# mainboard.net
KiCad netlist of a schematic drawn in EAGLE
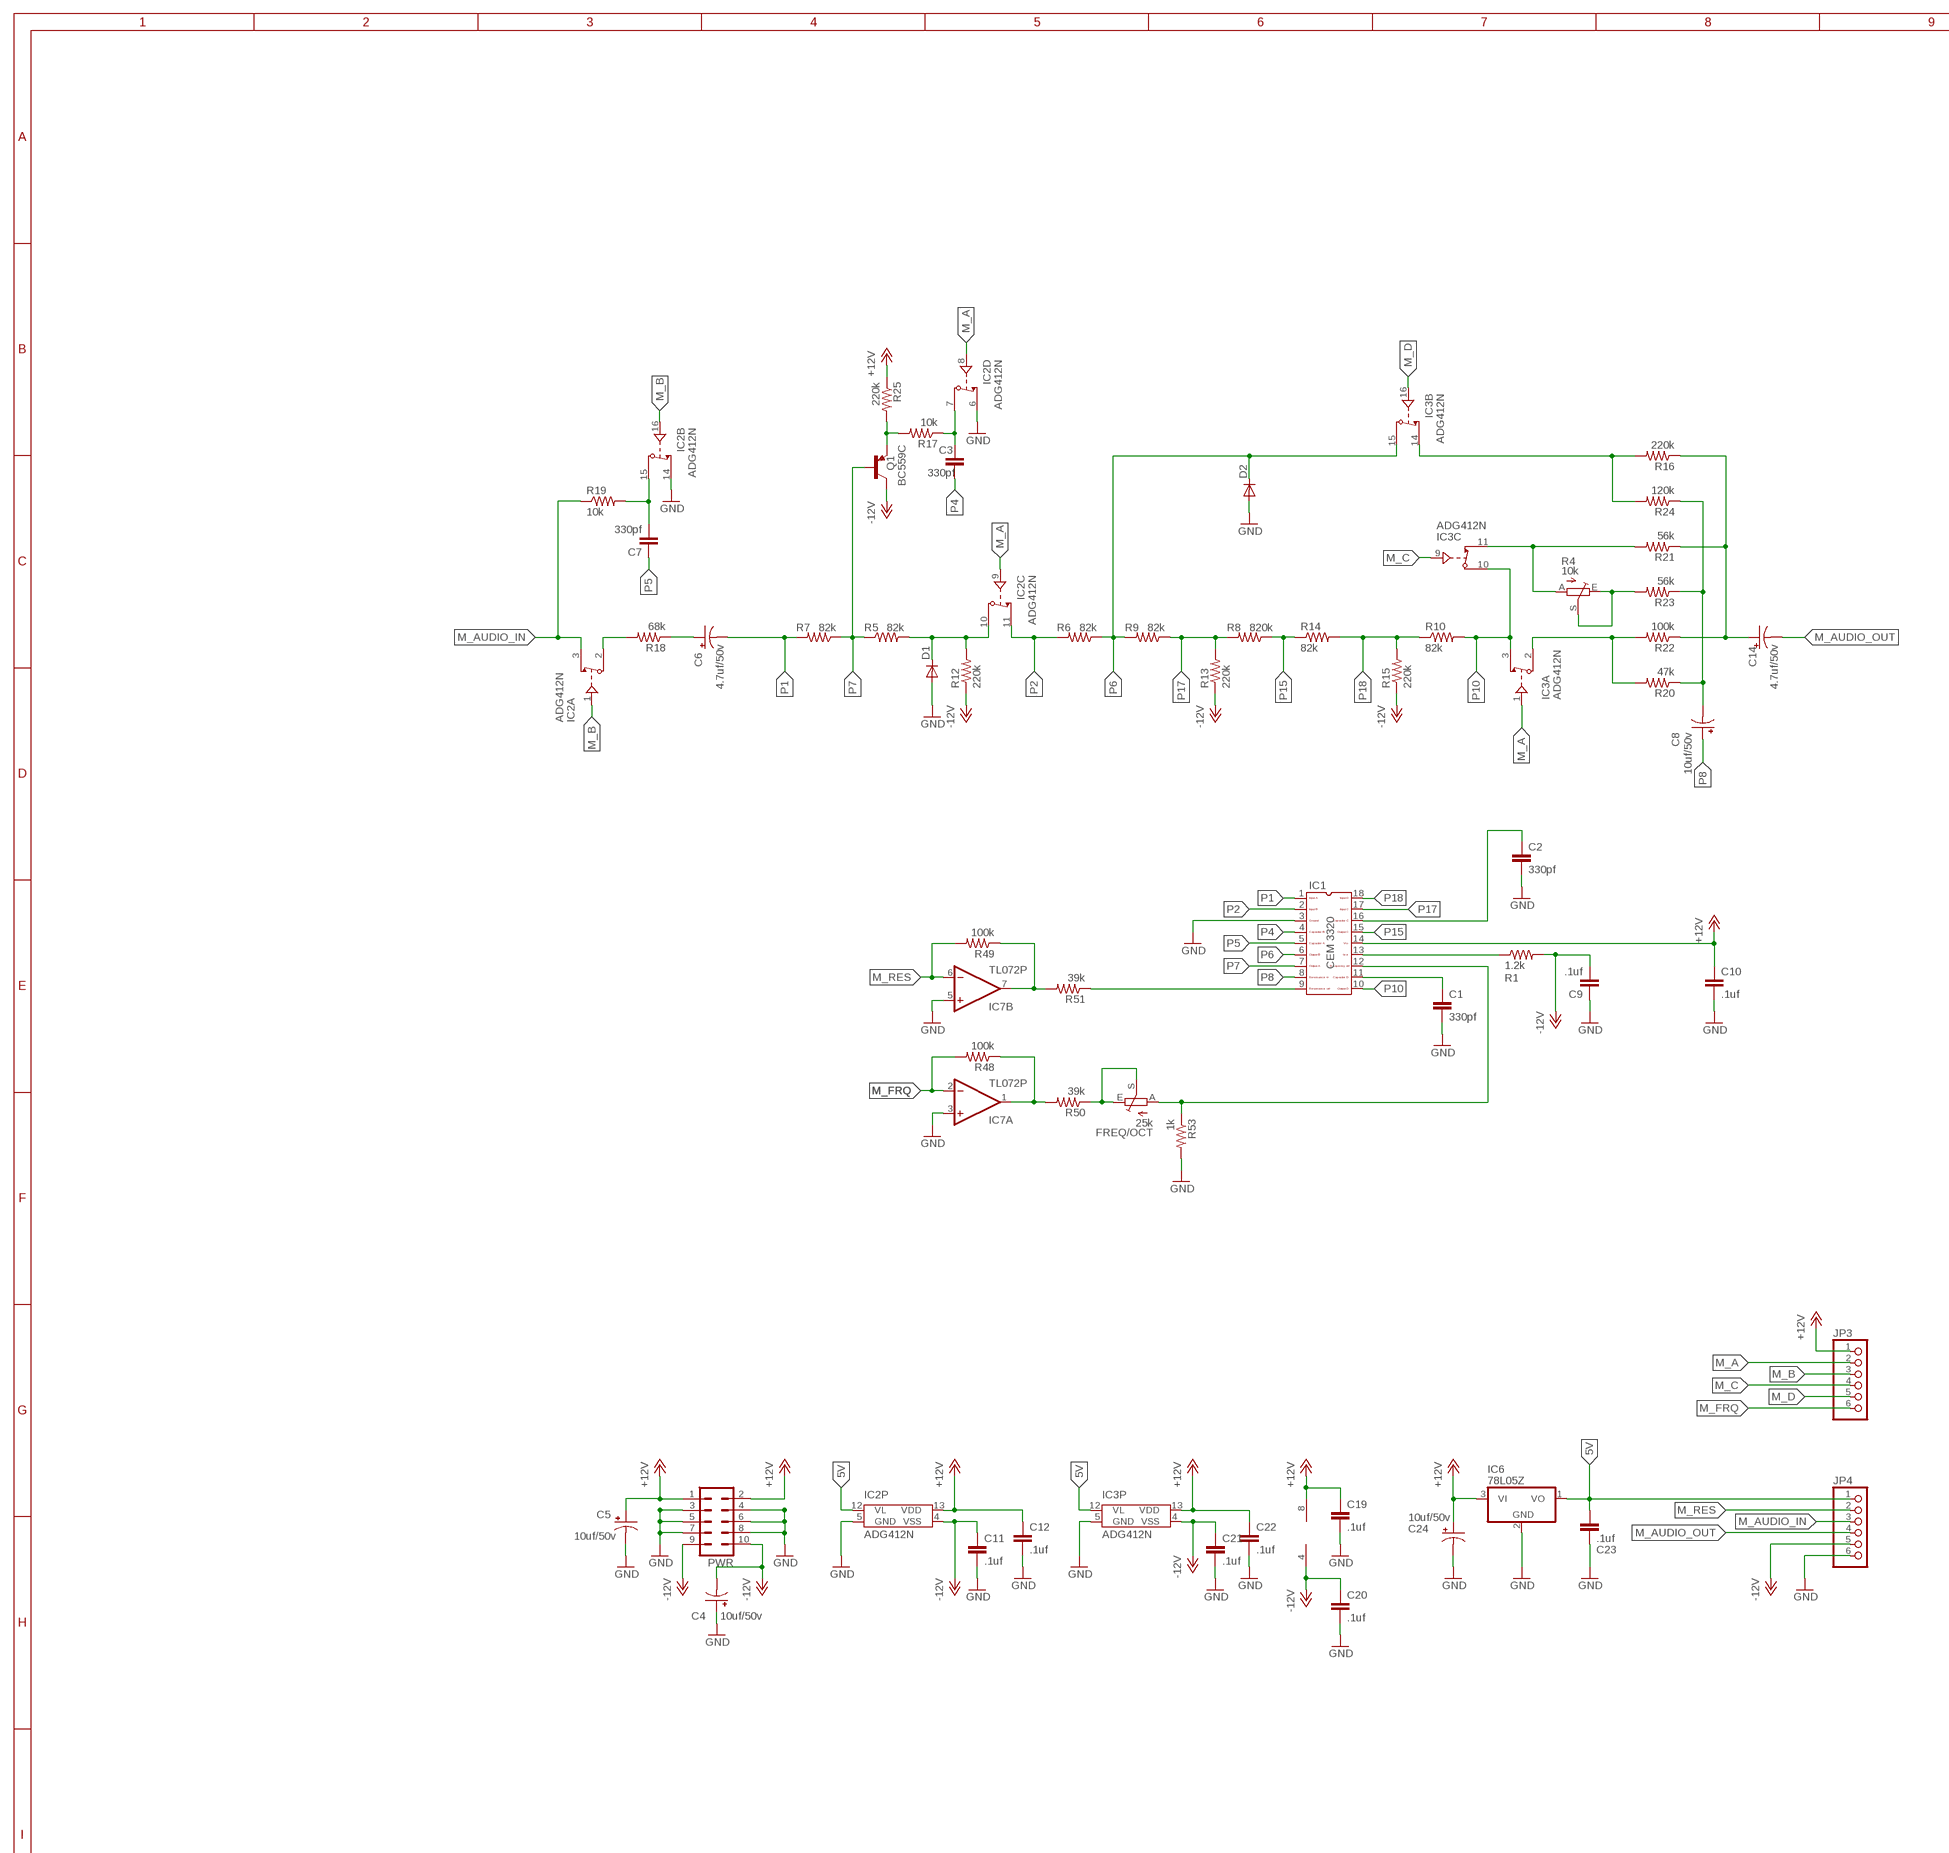
[diagram p0: schematic, sheet 1, part 1 of 2]
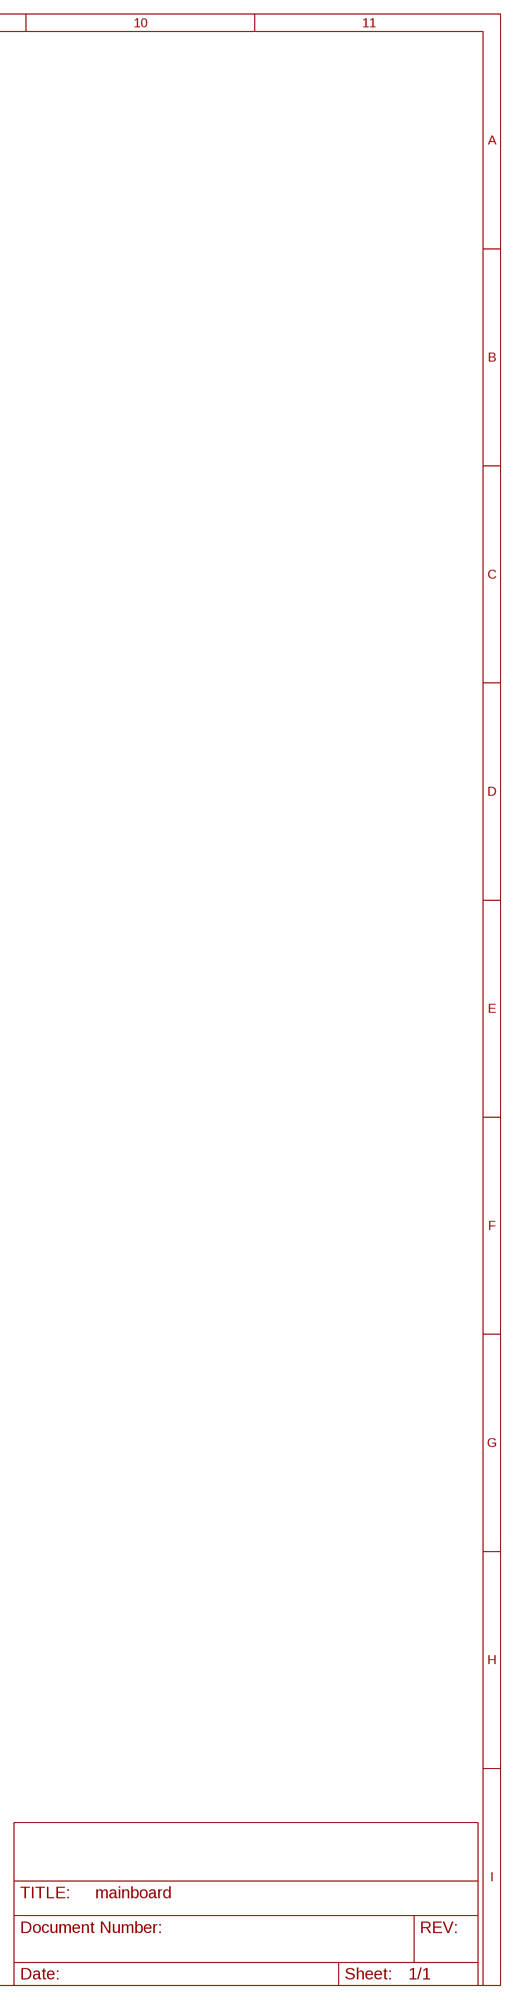
[diagram p1: schematic, sheet 1, part 2 of 2]

(export (version "E")
  (design (tool "Eeschema 10.0.6"))
  (components
    (comp (ref "C1")
      (value "330pf")
      (footprint "eagle-import:C050-050X075")
      (libsource (lib "eagle-import") (part "C-EU050-050X075"))
    )
    (comp (ref "C2")
      (value "330pf")
      (footprint "eagle-import:C050-050X075")
      (libsource (lib "eagle-import") (part "C-EU050-050X075"))
    )
    (comp (ref "C3")
      (value "330pf")
      (footprint "eagle-import:C050-050X075")
      (libsource (lib "eagle-import") (part "C-EU050-050X075"))
    )
    (comp (ref "C4")
      (value "10uf/50v")
      (footprint "eagle-import:E2,5-5")
      (libsource (lib "eagle-import") (part "CPOL-USE2.5-5"))
    )
    (comp (ref "C5")
      (value "10uf/50v")
      (footprint "eagle-import:E2,5-5")
      (libsource (lib "eagle-import") (part "CPOL-USE2.5-5"))
    )
    (comp (ref "C6")
      (value "4.7uf/50v")
      (footprint "eagle-import:E2,5-5")
      (libsource (lib "eagle-import") (part "CPOL-USE2.5-5"))
    )
    (comp (ref "C7")
      (value "330pf")
      (footprint "eagle-import:C050-050X075")
      (libsource (lib "eagle-import") (part "C-EU050-050X075"))
    )
    (comp (ref "C8")
      (value "10uf/50v")
      (footprint "eagle-import:E2,5-5")
      (libsource (lib "eagle-import") (part "CPOL-USE2.5-5"))
    )
    (comp (ref "C9")
      (value ".1uf")
      (footprint "eagle-import:C050-024X044")
      (libsource (lib "eagle-import") (part "resistor_C-EU050-024X044"))
    )
    (comp (ref "C10")
      (value ".1uf")
      (footprint "eagle-import:C050-024X044")
      (libsource (lib "eagle-import") (part "resistor_C-EU050-024X044"))
    )
    (comp (ref "C11")
      (value ".1uf")
      (footprint "eagle-import:C050-024X044")
      (libsource (lib "eagle-import") (part "resistor_C-EU050-024X044"))
    )
    (comp (ref "C12")
      (value ".1uf")
      (footprint "eagle-import:C050-024X044")
      (libsource (lib "eagle-import") (part "resistor_C-EU050-024X044"))
    )
    (comp (ref "C14")
      (value "4.7uf/50v")
      (footprint "eagle-import:E2,5-5")
      (libsource (lib "eagle-import") (part "CPOL-USE2.5-5"))
    )
    (comp (ref "C19")
      (value ".1uf")
      (footprint "eagle-import:C050-024X044")
      (libsource (lib "eagle-import") (part "resistor_C-EU050-024X044"))
    )
    (comp (ref "C20")
      (value ".1uf")
      (footprint "eagle-import:C050-024X044")
      (libsource (lib "eagle-import") (part "resistor_C-EU050-024X044"))
    )
    (comp (ref "C21")
      (value ".1uf")
      (footprint "eagle-import:C050-024X044")
      (libsource (lib "eagle-import") (part "resistor_C-EU050-024X044"))
    )
    (comp (ref "C22")
      (value ".1uf")
      (footprint "eagle-import:C050-024X044")
      (libsource (lib "eagle-import") (part "resistor_C-EU050-024X044"))
    )
    (comp (ref "C23")
      (value ".1uf")
      (footprint "eagle-import:C050-024X044")
      (libsource (lib "eagle-import") (part "resistor_C-EU050-024X044"))
    )
    (comp (ref "C24")
      (value "10uf/50v")
      (footprint "eagle-import:E2,5-5")
      (libsource (lib "eagle-import") (part "CPOL-USE2.5-5"))
    )
    (comp (ref "D1")
      (value "1N4148DO35-7")
      (footprint "eagle-import:DO35-7")
      (libsource (lib "eagle-import") (part "1N4148DO35-7"))
    )
    (comp (ref "D2")
      (value "1N4148DO35-7")
      (footprint "eagle-import:DO35-7")
      (libsource (lib "eagle-import") (part "1N4148DO35-7"))
    )
    (comp (ref "FREQ/OCT")
      (value "25k")
      (footprint "eagle-import:S64YW")
      (libsource (lib "eagle-import") (part "TRIM_1234-S64YW"))
    )
    (comp (ref "IC1")
      (value "CEM3320")
      (footprint "eagle-import:DIL18")
      (libsource (lib "eagle-import") (part "CEM3320"))
    )
    (comp (ref "IC2")
      (value "ADG412N")
      (footprint "eagle-import:DIL16")
      (fields (field (name "MF") "ALTERA CORPORATION") (field (name "MPN") "ADG412TQ"))
      (libsource (lib "eagle-import") (part "ADG412N"))
    )
    (comp (ref "IC3")
      (value "ADG412N")
      (footprint "eagle-import:DIL16")
      (fields (field (name "MF") "ALTERA CORPORATION") (field (name "MPN") "ADG412TQ"))
      (libsource (lib "eagle-import") (part "ADG412N"))
    )
    (comp (ref "IC6")
      (value "78L05Z")
      (footprint "eagle-import:TO92")
      (libsource (lib "eagle-import") (part "78ZL05"))
    )
    (comp (ref "IC7")
      (value "TL072P")
      (footprint "eagle-import:DIL08")
      (libsource (lib "eagle-import") (part "TL072P"))
    )
    (comp (ref "JP3")
      (value "PINHD-1X6")
      (footprint "eagle-import:1X06")
      (libsource (lib "eagle-import") (part "PINHD-1X6"))
    )
    (comp (ref "JP4")
      (value "PINHD-1X6")
      (footprint "eagle-import:1X06")
      (libsource (lib "eagle-import") (part "PINHD-1X6"))
    )
    (comp (ref "PWR")
      (value "ML10")
      (footprint "eagle-import:ML10")
      (libsource (lib "eagle-import") (part "ML10"))
    )
    (comp (ref "Q1")
      (value "BC559C")
      (footprint "eagle-import:TO92-EBC")
      (libsource (lib "eagle-import") (part "BC559C"))
    )
    (comp (ref "R1")
      (value "1.2k")
      (footprint "eagle-import:0207_10")
      (libsource (lib "eagle-import") (part "R-US_0207/10"))
    )
    (comp (ref "R4")
      (value "10k")
      (footprint "eagle-import:S64YW")
      (libsource (lib "eagle-import") (part "TRIM_1234-S64YW"))
    )
    (comp (ref "R5")
      (value "82k")
      (footprint "eagle-import:0207_10")
      (libsource (lib "eagle-import") (part "R-US_0207/10"))
    )
    (comp (ref "R6")
      (value "82k")
      (footprint "eagle-import:0207_10")
      (libsource (lib "eagle-import") (part "R-US_0207/10"))
    )
    (comp (ref "R7")
      (value "82k")
      (footprint "eagle-import:0207_10")
      (libsource (lib "eagle-import") (part "R-US_0207/10"))
    )
    (comp (ref "R8")
      (value "820k")
      (footprint "eagle-import:0207_10")
      (libsource (lib "eagle-import") (part "R-US_0207/10"))
    )
    (comp (ref "R9")
      (value "82k")
      (footprint "eagle-import:0207_10")
      (libsource (lib "eagle-import") (part "R-US_0207/10"))
    )
    (comp (ref "R10")
      (value "82k")
      (footprint "eagle-import:0207_10")
      (libsource (lib "eagle-import") (part "R-US_0207/10"))
    )
    (comp (ref "R12")
      (value "220k")
      (footprint "eagle-import:0207_10")
      (libsource (lib "eagle-import") (part "R-US_0207/10"))
    )
    (comp (ref "R13")
      (value "220k")
      (footprint "eagle-import:0207_10")
      (libsource (lib "eagle-import") (part "R-US_0207/10"))
    )
    (comp (ref "R14")
      (value "82k")
      (footprint "eagle-import:0207_10")
      (libsource (lib "eagle-import") (part "R-US_0207/10"))
    )
    (comp (ref "R15")
      (value "220k")
      (footprint "eagle-import:0207_10")
      (libsource (lib "eagle-import") (part "R-US_0207/10"))
    )
    (comp (ref "R16")
      (value "220k")
      (footprint "eagle-import:0207_10")
      (libsource (lib "eagle-import") (part "R-US_0207/10"))
    )
    (comp (ref "R17")
      (value "10k")
      (footprint "eagle-import:0207_10")
      (libsource (lib "eagle-import") (part "R-US_0207/10"))
    )
    (comp (ref "R18")
      (value "68k")
      (footprint "eagle-import:0207_10")
      (libsource (lib "eagle-import") (part "R-US_0207/10"))
    )
    (comp (ref "R19")
      (value "10k")
      (footprint "eagle-import:0207_10")
      (libsource (lib "eagle-import") (part "R-US_0207/10"))
    )
    (comp (ref "R20")
      (value "47k")
      (footprint "eagle-import:0207_10")
      (libsource (lib "eagle-import") (part "R-US_0207/10"))
    )
    (comp (ref "R21")
      (value "56k")
      (footprint "eagle-import:0207_10")
      (libsource (lib "eagle-import") (part "R-US_0207/10"))
    )
    (comp (ref "R22")
      (value "100k")
      (footprint "eagle-import:0207_10")
      (libsource (lib "eagle-import") (part "R-US_0207/10"))
    )
    (comp (ref "R23")
      (value "56k")
      (footprint "eagle-import:0207_10")
      (libsource (lib "eagle-import") (part "R-US_0207/10"))
    )
    (comp (ref "R24")
      (value "120k")
      (footprint "eagle-import:0207_10")
      (libsource (lib "eagle-import") (part "R-US_0207/10"))
    )
    (comp (ref "R25")
      (value "220k")
      (footprint "eagle-import:0207_10")
      (libsource (lib "eagle-import") (part "R-US_0207/10"))
    )
    (comp (ref "R48")
      (value "100k")
      (footprint "eagle-import:0207_10")
      (libsource (lib "eagle-import") (part "R-US_0207/10"))
    )
    (comp (ref "R49")
      (value "100k")
      (footprint "eagle-import:0207_10")
      (libsource (lib "eagle-import") (part "R-US_0207/10"))
    )
    (comp (ref "R50")
      (value "39k")
      (footprint "eagle-import:0207_10")
      (libsource (lib "eagle-import") (part "R-US_0207/10"))
    )
    (comp (ref "R51")
      (value "39k")
      (footprint "eagle-import:0207_10")
      (libsource (lib "eagle-import") (part "R-US_0207/10"))
    )
    (comp (ref "R53")
      (value "1k")
      (footprint "eagle-import:0207_10")
      (libsource (lib "eagle-import") (part "R-US_0207/10"))
    )
  )
  (nets
    (net (code "1") (name "+12V") (class "Default")
      (node (ref "C10") (pin "1") (pinfunction "1_1") (pintype "passive"))
      (node (ref "C12") (pin "1") (pinfunction "1_1") (pintype "passive"))
      (node (ref "C19") (pin "1") (pinfunction "1_1") (pintype "passive"))
      (node (ref "C22") (pin "1") (pinfunction "1_1") (pintype "passive"))
      (node (ref "C24") (pin "+") (pinfunction "+_+") (pintype "passive"))
      (node (ref "C5") (pin "+") (pinfunction "+_+") (pintype "passive"))
      (node (ref "IC1") (pin "14") (pinfunction "14_14") (pintype "power_in"))
      (node (ref "IC2") (pin "13") (pinfunction "VDD_13") (pintype "power_in"))
      (node (ref "IC3") (pin "13") (pinfunction "VDD_13") (pintype "power_in"))
      (node (ref "IC6") (pin "3") (pinfunction "VI_3") (pintype "input"))
      (node (ref "IC7") (pin "8") (pinfunction "V+_8") (pintype "power_in"))
      (node (ref "JP3") (pin "1") (pinfunction "1_1") (pintype "passive"))
      (node (ref "PWR") (pin "1") (pinfunction "1_1") (pintype "passive"))
      (node (ref "PWR") (pin "2") (pinfunction "2_2") (pintype "passive"))
      (node (ref "R25") (pin "1") (pinfunction "1_1") (pintype "passive"))
    )
    (net (code "2") (name "-12V") (class "Default")
      (node (ref "C11") (pin "1") (pinfunction "1_1") (pintype "passive"))
      (node (ref "C20") (pin "1") (pinfunction "1_1") (pintype "passive"))
      (node (ref "C21") (pin "1") (pinfunction "1_1") (pintype "passive"))
      (node (ref "C4") (pin "-") (pinfunction "-_-") (pintype "passive"))
      (node (ref "C9") (pin "2") (pinfunction "2_2") (pintype "passive"))
      (node (ref "IC2") (pin "4") (pinfunction "VSS_4") (pintype "power_in"))
      (node (ref "IC3") (pin "4") (pinfunction "VSS_4") (pintype "power_in"))
      (node (ref "IC7") (pin "4") (pinfunction "V-_4") (pintype "power_in"))
      (node (ref "JP4") (pin "5") (pinfunction "5_5") (pintype "passive"))
      (node (ref "PWR") (pin "10") (pinfunction "10_10") (pintype "passive"))
      (node (ref "PWR") (pin "9") (pinfunction "9_9") (pintype "passive"))
      (node (ref "Q1") (pin "C") (pinfunction "C_C") (pintype "passive"))
      (node (ref "R1") (pin "2") (pinfunction "2_2") (pintype "passive"))
      (node (ref "R12") (pin "1") (pinfunction "1_1") (pintype "passive"))
      (node (ref "R13") (pin "1") (pinfunction "1_1") (pintype "passive"))
      (node (ref "R15") (pin "1") (pinfunction "1_1") (pintype "passive"))
    )
    (net (code "3") (name "5V") (class "Default")
      (node (ref "C23") (pin "1") (pinfunction "1_1") (pintype "passive"))
      (node (ref "IC2") (pin "12") (pinfunction "VL_12") (pintype "power_in"))
      (node (ref "IC3") (pin "12") (pinfunction "VL_12") (pintype "power_in"))
      (node (ref "IC6") (pin "1") (pinfunction "VO_1") (pintype "passive"))
      (node (ref "JP4") (pin "1") (pinfunction "1_1") (pintype "passive"))
    )
    (net (code "4") (name "GND") (class "Default")
      (node (ref "C1") (pin "1") (pinfunction "1_1") (pintype "passive"))
      (node (ref "C10") (pin "2") (pinfunction "2_2") (pintype "passive"))
      (node (ref "C11") (pin "2") (pinfunction "2_2") (pintype "passive"))
      (node (ref "C12") (pin "2") (pinfunction "2_2") (pintype "passive"))
      (node (ref "C19") (pin "2") (pinfunction "2_2") (pintype "passive"))
      (node (ref "C2") (pin "2") (pinfunction "2_2") (pintype "passive"))
      (node (ref "C20") (pin "2") (pinfunction "2_2") (pintype "passive"))
      (node (ref "C21") (pin "2") (pinfunction "2_2") (pintype "passive"))
      (node (ref "C22") (pin "2") (pinfunction "2_2") (pintype "passive"))
      (node (ref "C23") (pin "2") (pinfunction "2_2") (pintype "passive"))
      (node (ref "C24") (pin "-") (pinfunction "-_-") (pintype "passive"))
      (node (ref "C4") (pin "+") (pinfunction "+_+") (pintype "passive"))
      (node (ref "C5") (pin "-") (pinfunction "-_-") (pintype "passive"))
      (node (ref "C9") (pin "1") (pinfunction "1_1") (pintype "passive"))
      (node (ref "D1") (pin "A") (pinfunction "A_A") (pintype "passive"))
      (node (ref "D2") (pin "A") (pinfunction "A_A") (pintype "passive"))
      (node (ref "IC1") (pin "3") (pinfunction "3_3") (pintype "power_in"))
      (node (ref "IC2") (pin "14") (pinfunction "S_14") (pintype "passive"))
      (node (ref "IC2") (pin "5") (pinfunction "GND_5") (pintype "power_in"))
      (node (ref "IC2") (pin "6") (pinfunction "S_6") (pintype "passive"))
      (node (ref "IC3") (pin "5") (pinfunction "GND_5") (pintype "power_in"))
      (node (ref "IC6") (pin "2") (pinfunction "GND_2") (pintype "passive"))
      (node (ref "IC7") (pin "3") (pinfunction "+IN_3") (pintype "input"))
      (node (ref "IC7") (pin "5") (pinfunction "+IN_5") (pintype "input"))
      (node (ref "JP4") (pin "6") (pinfunction "6_6") (pintype "passive"))
      (node (ref "PWR") (pin "3") (pinfunction "3_3") (pintype "passive"))
      (node (ref "PWR") (pin "4") (pinfunction "4_4") (pintype "passive"))
      (node (ref "PWR") (pin "5") (pinfunction "5_5") (pintype "passive"))
      (node (ref "PWR") (pin "6") (pinfunction "6_6") (pintype "passive"))
      (node (ref "PWR") (pin "7") (pinfunction "7_7") (pintype "passive"))
      (node (ref "PWR") (pin "8") (pinfunction "8_8") (pintype "passive"))
      (node (ref "R53") (pin "2") (pinfunction "2_2") (pintype "passive"))
    )
    (net (code "5") (name "M_A") (class "Default")
      (node (ref "IC2") (pin "8") (pinfunction "IN_8") (pintype "input"))
      (node (ref "IC2") (pin "9") (pinfunction "IN_9") (pintype "input"))
      (node (ref "IC3") (pin "1") (pinfunction "IN_1") (pintype "input"))
      (node (ref "JP3") (pin "2") (pinfunction "2_2") (pintype "passive"))
    )
    (net (code "6") (name "M_AUDIO_IN") (class "Default")
      (node (ref "IC2") (pin "3") (pinfunction "S_3") (pintype "passive"))
      (node (ref "JP4") (pin "3") (pinfunction "3_3") (pintype "passive"))
      (node (ref "R19") (pin "1") (pinfunction "1_1") (pintype "passive"))
    )
    (net (code "7") (name "M_AUDIO_OUT") (class "Default")
      (node (ref "C14") (pin "-") (pinfunction "-_-") (pintype "passive"))
      (node (ref "JP4") (pin "4") (pinfunction "4_4") (pintype "passive"))
    )
    (net (code "8") (name "M_B") (class "Default")
      (node (ref "IC2") (pin "1") (pinfunction "IN_1") (pintype "input"))
      (node (ref "IC2") (pin "16") (pinfunction "IN_16") (pintype "input"))
      (node (ref "JP3") (pin "3") (pinfunction "3_3") (pintype "passive"))
    )
    (net (code "9") (name "M_C") (class "Default")
      (node (ref "IC3") (pin "9") (pinfunction "IN_9") (pintype "input"))
      (node (ref "JP3") (pin "4") (pinfunction "4_4") (pintype "passive"))
    )
    (net (code "10") (name "M_D") (class "Default")
      (node (ref "IC3") (pin "16") (pinfunction "IN_16") (pintype "input"))
      (node (ref "JP3") (pin "5") (pinfunction "5_5") (pintype "passive"))
    )
    (net (code "11") (name "M_FRQ") (class "Default")
      (node (ref "IC7") (pin "2") (pinfunction "-IN_2") (pintype "input"))
      (node (ref "JP3") (pin "6") (pinfunction "6_6") (pintype "passive"))
      (node (ref "R48") (pin "2") (pinfunction "2_2") (pintype "passive"))
    )
    (net (code "12") (name "M_RES") (class "Default")
      (node (ref "IC7") (pin "6") (pinfunction "-IN_6") (pintype "input"))
      (node (ref "JP4") (pin "2") (pinfunction "2_2") (pintype "passive"))
      (node (ref "R49") (pin "2") (pinfunction "2_2") (pintype "passive"))
    )
    (net (code "13") (name "Net-(C1-Pad2)") (class "Default")
      (node (ref "C1") (pin "2") (pinfunction "2_2") (pintype "passive"))
      (node (ref "IC1") (pin "11") (pinfunction "11_11") (pintype "output"))
    )
    (net (code "14") (name "Net-(C2-Pad1)") (class "Default")
      (node (ref "C2") (pin "1") (pinfunction "1_1") (pintype "passive"))
      (node (ref "IC1") (pin "16") (pinfunction "16_16") (pintype "bidirectional"))
    )
    (net (code "15") (name "Net-(C6-Pad+)") (class "Default")
      (node (ref "C6") (pin "+") (pinfunction "+_+") (pintype "passive"))
      (node (ref "R18") (pin "1") (pinfunction "1_1") (pintype "passive"))
    )
    (net (code "16") (name "Net-(C8-Pad-)") (class "Default")
      (node (ref "C8") (pin "-") (pinfunction "-_-") (pintype "passive"))
      (node (ref "R20") (pin "1") (pinfunction "1_1") (pintype "passive"))
      (node (ref "R23") (pin "1") (pinfunction "1_1") (pintype "passive"))
      (node (ref "R24") (pin "1") (pinfunction "1_1") (pintype "passive"))
    )
    (net (code "17") (name "Net-(C14-Pad+)") (class "Default")
      (node (ref "C14") (pin "+") (pinfunction "+_+") (pintype "passive"))
      (node (ref "R16") (pin "1") (pinfunction "1_1") (pintype "passive"))
      (node (ref "R21") (pin "1") (pinfunction "1_1") (pintype "passive"))
      (node (ref "R22") (pin "1") (pinfunction "1_1") (pintype "passive"))
    )
    (net (code "18") (name "Net-(FREQ/OCT-PadA)") (class "Default")
      (node (ref "FREQ/OCT") (pin "A") (pinfunction "A_A") (pintype "passive"))
      (node (ref "IC1") (pin "12") (pinfunction "12_12") (pintype "bidirectional"))
      (node (ref "R53") (pin "1") (pinfunction "1_1") (pintype "passive"))
    )
    (net (code "19") (name "Net-(FREQ/OCT-PadE)") (class "Default")
      (node (ref "FREQ/OCT") (pin "E") (pinfunction "E_E") (pintype "passive"))
      (node (ref "FREQ/OCT") (pin "S") (pinfunction "S_S") (pintype "passive"))
      (node (ref "R50") (pin "1") (pinfunction "1_1") (pintype "passive"))
    )
    (net (code "20") (name "Net-(IC1-Pad9)") (class "Default")
      (node (ref "IC1") (pin "9") (pinfunction "9_9") (pintype "input"))
      (node (ref "R51") (pin "1") (pinfunction "1_1") (pintype "passive"))
    )
    (net (code "21") (name "Net-(IC1-Pad13)") (class "Default")
      (node (ref "IC1") (pin "13") (pinfunction "13_13") (pintype "power_in"))
      (node (ref "R1") (pin "1") (pinfunction "1_1") (pintype "passive"))
    )
    (net (code "22") (name "Net-(IC2A-D)") (class "Default")
      (node (ref "IC2") (pin "2") (pinfunction "D_2") (pintype "passive"))
      (node (ref "R18") (pin "2") (pinfunction "2_2") (pintype "passive"))
    )
    (net (code "23") (name "Net-(IC2B-D)") (class "Default")
      (node (ref "C7") (pin "2") (pinfunction "2_2") (pintype "passive"))
      (node (ref "IC2") (pin "15") (pinfunction "D_15") (pintype "passive"))
      (node (ref "R19") (pin "2") (pinfunction "2_2") (pintype "passive"))
    )
    (net (code "24") (name "Net-(IC2C-D)") (class "Default")
      (node (ref "D1") (pin "C") (pinfunction "C_C") (pintype "passive"))
      (node (ref "IC2") (pin "10") (pinfunction "D_10") (pintype "passive"))
      (node (ref "R12") (pin "2") (pinfunction "2_2") (pintype "passive"))
      (node (ref "R5") (pin "2") (pinfunction "2_2") (pintype "passive"))
    )
    (net (code "25") (name "Net-(IC2D-D)") (class "Default")
      (node (ref "C3") (pin "1") (pinfunction "1_1") (pintype "passive"))
      (node (ref "IC2") (pin "7") (pinfunction "D_7") (pintype "passive"))
      (node (ref "R17") (pin "1") (pinfunction "1_1") (pintype "passive"))
    )
    (net (code "26") (name "Net-(IC3A-D)") (class "Default")
      (node (ref "IC3") (pin "2") (pinfunction "D_2") (pintype "passive"))
      (node (ref "R20") (pin "2") (pinfunction "2_2") (pintype "passive"))
      (node (ref "R22") (pin "2") (pinfunction "2_2") (pintype "passive"))
    )
    (net (code "27") (name "Net-(IC3B-S)") (class "Default")
      (node (ref "IC3") (pin "14") (pinfunction "S_14") (pintype "passive"))
      (node (ref "R16") (pin "2") (pinfunction "2_2") (pintype "passive"))
      (node (ref "R24") (pin "2") (pinfunction "2_2") (pintype "passive"))
    )
    (net (code "28") (name "Net-(IC3C-S)") (class "Default")
      (node (ref "IC3") (pin "11") (pinfunction "S_11") (pintype "passive"))
      (node (ref "R21") (pin "2") (pinfunction "2_2") (pintype "passive"))
      (node (ref "R4") (pin "A") (pinfunction "A_A") (pintype "passive"))
    )
    (net (code "29") (name "Net-(IC7A-OUT)") (class "Default")
      (node (ref "IC7") (pin "1") (pinfunction "OUT_1") (pintype "output"))
      (node (ref "R48") (pin "1") (pinfunction "1_1") (pintype "passive"))
      (node (ref "R50") (pin "2") (pinfunction "2_2") (pintype "passive"))
    )
    (net (code "30") (name "Net-(IC7B-OUT)") (class "Default")
      (node (ref "IC7") (pin "7") (pinfunction "OUT_7") (pintype "output"))
      (node (ref "R49") (pin "1") (pinfunction "1_1") (pintype "passive"))
      (node (ref "R51") (pin "2") (pinfunction "2_2") (pintype "passive"))
    )
    (net (code "31") (name "Net-(Q1-PadE)") (class "Default")
      (node (ref "Q1") (pin "E") (pinfunction "E_E") (pintype "passive"))
      (node (ref "R17") (pin "2") (pinfunction "2_2") (pintype "passive"))
      (node (ref "R25") (pin "2") (pinfunction "2_2") (pintype "passive"))
    )
    (net (code "32") (name "Net-(R23-Pad2)") (class "Default")
      (node (ref "R23") (pin "2") (pinfunction "2_2") (pintype "passive"))
      (node (ref "R4") (pin "E") (pinfunction "E_E") (pintype "passive"))
      (node (ref "R4") (pin "S") (pinfunction "S_S") (pintype "passive"))
    )
    (net (code "33") (name "P1") (class "Default")
      (node (ref "C6") (pin "-") (pinfunction "-_-") (pintype "passive"))
      (node (ref "IC1") (pin "1") (pinfunction "1_1") (pintype "input"))
      (node (ref "R7") (pin "2") (pinfunction "2_2") (pintype "passive"))
    )
    (net (code "34") (name "P2") (class "Default")
      (node (ref "IC1") (pin "2") (pinfunction "2_2") (pintype "input"))
      (node (ref "IC2") (pin "11") (pinfunction "S_11") (pintype "passive"))
      (node (ref "R6") (pin "2") (pinfunction "2_2") (pintype "passive"))
    )
    (net (code "35") (name "P4") (class "Default")
      (node (ref "C3") (pin "2") (pinfunction "2_2") (pintype "passive"))
      (node (ref "IC1") (pin "4") (pinfunction "4_4") (pintype "bidirectional"))
    )
    (net (code "36") (name "P5") (class "Default")
      (node (ref "C7") (pin "1") (pinfunction "1_1") (pintype "passive"))
      (node (ref "IC1") (pin "5") (pinfunction "5_5") (pintype "bidirectional"))
    )
    (net (code "37") (name "P6") (class "Default")
      (node (ref "D2") (pin "C") (pinfunction "C_C") (pintype "passive"))
      (node (ref "IC1") (pin "6") (pinfunction "6_6") (pintype "output"))
      (node (ref "IC3") (pin "15") (pinfunction "D_15") (pintype "passive"))
      (node (ref "R6") (pin "1") (pinfunction "1_1") (pintype "passive"))
      (node (ref "R9") (pin "2") (pinfunction "2_2") (pintype "passive"))
    )
    (net (code "38") (name "P7") (class "Default")
      (node (ref "IC1") (pin "7") (pinfunction "7_7") (pintype "output"))
      (node (ref "Q1") (pin "B") (pinfunction "B_B") (pintype "passive"))
      (node (ref "R5") (pin "1") (pinfunction "1_1") (pintype "passive"))
      (node (ref "R7") (pin "1") (pinfunction "1_1") (pintype "passive"))
    )
    (net (code "39") (name "P8") (class "Default")
      (node (ref "C8") (pin "+") (pinfunction "+_+") (pintype "passive"))
      (node (ref "IC1") (pin "8") (pinfunction "8_8") (pintype "input"))
    )
    (net (code "40") (name "P10") (class "Default")
      (node (ref "IC1") (pin "10") (pinfunction "10_10") (pintype "output"))
      (node (ref "IC3") (pin "10") (pinfunction "D_10") (pintype "passive"))
      (node (ref "IC3") (pin "3") (pinfunction "S_3") (pintype "passive"))
      (node (ref "R10") (pin "2") (pinfunction "2_2") (pintype "passive"))
    )
    (net (code "41") (name "P15") (class "Default")
      (node (ref "IC1") (pin "15") (pinfunction "15_15") (pintype "output"))
      (node (ref "R14") (pin "1") (pinfunction "1_1") (pintype "passive"))
      (node (ref "R8") (pin "1") (pinfunction "1_1") (pintype "passive"))
    )
    (net (code "42") (name "P17") (class "Default")
      (node (ref "IC1") (pin "17") (pinfunction "17_17") (pintype "input"))
      (node (ref "R13") (pin "2") (pinfunction "2_2") (pintype "passive"))
      (node (ref "R8") (pin "2") (pinfunction "2_2") (pintype "passive"))
      (node (ref "R9") (pin "1") (pinfunction "1_1") (pintype "passive"))
    )
    (net (code "43") (name "P18") (class "Default")
      (node (ref "IC1") (pin "18") (pinfunction "18_18") (pintype "input"))
      (node (ref "R10") (pin "1") (pinfunction "1_1") (pintype "passive"))
      (node (ref "R14") (pin "2") (pinfunction "2_2") (pintype "passive"))
      (node (ref "R15") (pin "2") (pinfunction "2_2") (pintype "passive"))
    )
    (net (code "44") (name "unconnected-(FREQ/OCT-S-PadS@1)") (class "Default")
      (node (ref "FREQ/OCT") (pin "S@1") (pinfunction "S_S@1") (pintype "passive"))
    )
    (net (code "45") (name "unconnected-(R4-S-PadS@1)") (class "Default")
      (node (ref "R4") (pin "S@1") (pinfunction "S_S@1") (pintype "passive"))
    )
  )
)
